# spinkler_02.net
KiCad netlist of a schematic drawn in EAGLE
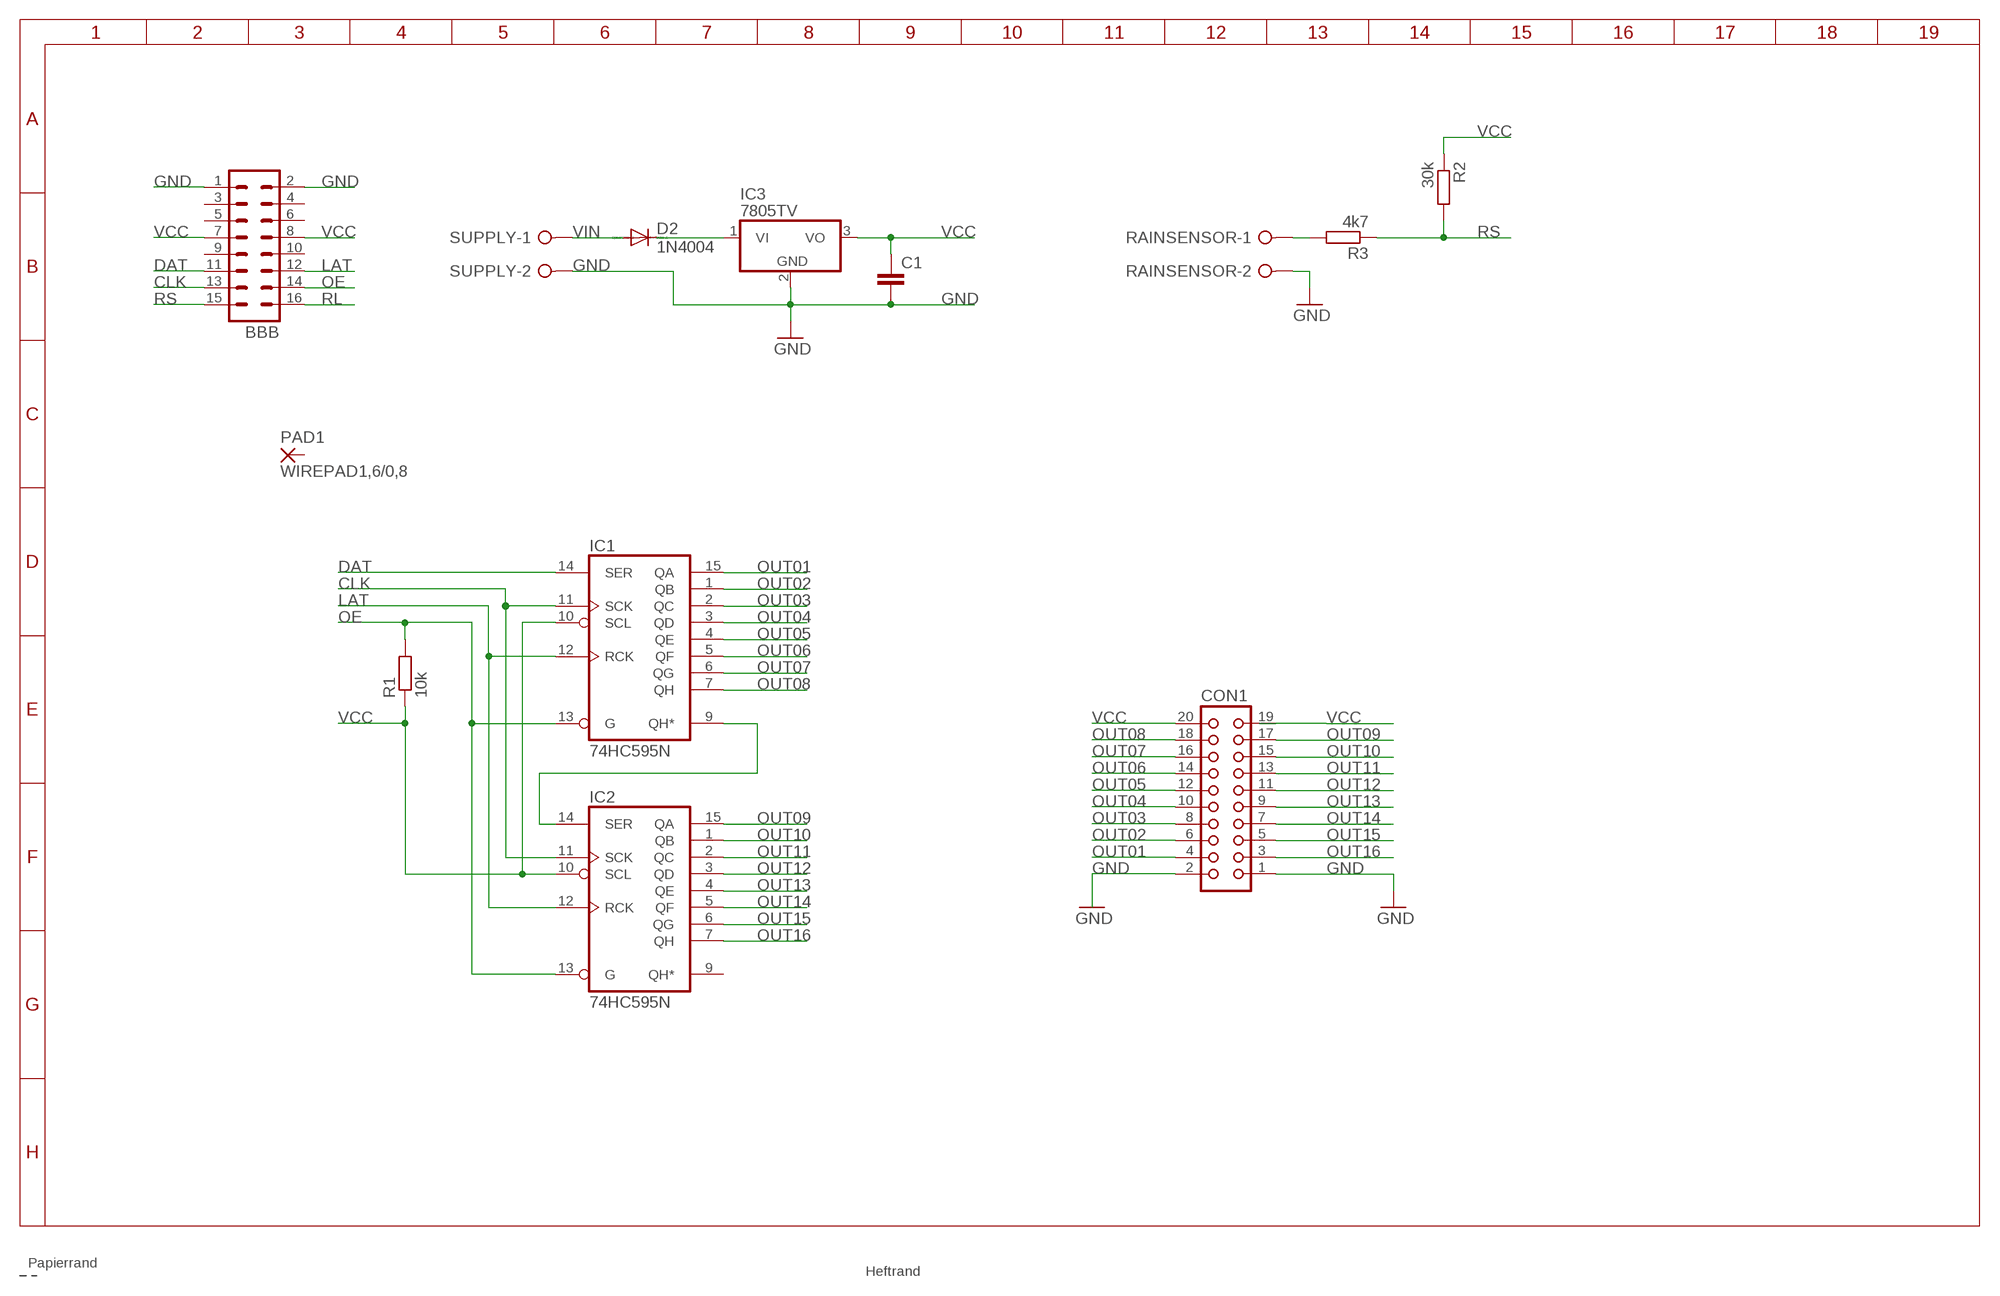
[diagram p0: schematic, sheet 1]

(export (version "E")
  (design (tool "Eeschema 10.0.6"))
  (components
    (comp (ref "BBB")
      (value "MA08-2")
      (footprint "eagle-import:MA08-2")
      (libsource (lib "eagle-import") (part "MA08-2"))
    )
    (comp (ref "C1")
      (value "C-EU050-025X075")
      (footprint "eagle-import:C050-025X075")
      (libsource (lib "eagle-import") (part "C-EU050-025X075"))
    )
    (comp (ref "CON1")
      (value "CON20")
      (footprint "eagle-import:CON20")
      (libsource (lib "eagle-import") (part "CON20"))
    )
    (comp (ref "D2")
      (value "1N4004")
      (footprint "eagle-import:DO41-10")
      (libsource (lib "eagle-import") (part "1N4004"))
    )
    (comp (ref "IC1")
      (value "74HC595N")
      (footprint "eagle-import:DIL16")
      (libsource (lib "eagle-import") (part "74595NHC"))
    )
    (comp (ref "IC2")
      (value "74HC595N")
      (footprint "eagle-import:DIL16")
      (libsource (lib "eagle-import") (part "74595NHC"))
    )
    (comp (ref "IC3")
      (value "7805TV")
      (footprint "eagle-import:TO220V")
      (libsource (lib "eagle-import") (part "78TV05"))
    )
    (comp (ref "PAD1")
      (value "WIREPAD1,6/0,8")
      (footprint "eagle-import:1,6_0,8")
      (libsource (lib "eagle-import") (part "WIREPAD1,6/0,8"))
    )
    (comp (ref "R1")
      (value "10k")
      (footprint "eagle-import:0207_10")
      (libsource (lib "eagle-import") (part "R-EU_0207/10"))
    )
    (comp (ref "R2")
      (value "30k")
      (footprint "eagle-import:0207_10")
      (libsource (lib "eagle-import") (part "R-EU_0207/10"))
    )
    (comp (ref "R3")
      (value "4k7")
      (footprint "eagle-import:0207_10")
      (libsource (lib "eagle-import") (part "R-EU_0207/10"))
    )
    (comp (ref "RAINSENSOR")
      (value "W237-02P")
      (footprint "eagle-import:W237-132")
      (libsource (lib "eagle-import") (part "W237-02P"))
    )
    (comp (ref "SUPPLY")
      (value "W237-02P")
      (footprint "eagle-import:W237-132")
      (libsource (lib "eagle-import") (part "W237-02P"))
    )
  )
  (nets
    (net (code "1") (name "/CLK") (class "Default")
      (node (ref "BBB") (pin "13") (pinfunction "13_13") (pintype "passive"))
      (node (ref "IC1") (pin "11") (pinfunction "SCK_11") (pintype "input"))
      (node (ref "IC2") (pin "11") (pinfunction "SCK_11") (pintype "input"))
    )
    (net (code "2") (name "/DAT") (class "Default")
      (node (ref "BBB") (pin "11") (pinfunction "11_11") (pintype "passive"))
      (node (ref "IC1") (pin "14") (pinfunction "SER_14") (pintype "input"))
    )
    (net (code "3") (name "/LAT") (class "Default")
      (node (ref "BBB") (pin "12") (pinfunction "12_12") (pintype "passive"))
      (node (ref "IC1") (pin "12") (pinfunction "RCK_12") (pintype "input"))
      (node (ref "IC2") (pin "12") (pinfunction "RCK_12") (pintype "input"))
    )
    (net (code "4") (name "/OE") (class "Default")
      (node (ref "BBB") (pin "14") (pinfunction "14_14") (pintype "passive"))
      (node (ref "IC1") (pin "13") (pinfunction "G_13") (pintype "input"))
      (node (ref "IC2") (pin "13") (pinfunction "G_13") (pintype "input"))
      (node (ref "R1") (pin "2") (pinfunction "2_2") (pintype "passive"))
    )
    (net (code "5") (name "/OUT01") (class "Default")
      (node (ref "CON1") (pin "4") (pinfunction "4_4") (pintype "passive"))
      (node (ref "IC1") (pin "15") (pinfunction "QA_15") (pintype "tri_state"))
    )
    (net (code "6") (name "/OUT02") (class "Default")
      (node (ref "CON1") (pin "6") (pinfunction "6_6") (pintype "passive"))
      (node (ref "IC1") (pin "1") (pinfunction "QB_1") (pintype "tri_state"))
    )
    (net (code "7") (name "/OUT03") (class "Default")
      (node (ref "CON1") (pin "8") (pinfunction "8_8") (pintype "passive"))
      (node (ref "IC1") (pin "2") (pinfunction "QC_2") (pintype "tri_state"))
    )
    (net (code "8") (name "/OUT04") (class "Default")
      (node (ref "CON1") (pin "10") (pinfunction "10_10") (pintype "passive"))
      (node (ref "IC1") (pin "3") (pinfunction "QD_3") (pintype "tri_state"))
    )
    (net (code "9") (name "/OUT05") (class "Default")
      (node (ref "CON1") (pin "12") (pinfunction "12_12") (pintype "passive"))
      (node (ref "IC1") (pin "4") (pinfunction "QE_4") (pintype "tri_state"))
    )
    (net (code "10") (name "/OUT06") (class "Default")
      (node (ref "CON1") (pin "14") (pinfunction "14_14") (pintype "passive"))
      (node (ref "IC1") (pin "5") (pinfunction "QF_5") (pintype "tri_state"))
    )
    (net (code "11") (name "/OUT07") (class "Default")
      (node (ref "CON1") (pin "16") (pinfunction "16_16") (pintype "passive"))
      (node (ref "IC1") (pin "6") (pinfunction "QG_6") (pintype "tri_state"))
    )
    (net (code "12") (name "/OUT08") (class "Default")
      (node (ref "CON1") (pin "18") (pinfunction "18_18") (pintype "passive"))
      (node (ref "IC1") (pin "7") (pinfunction "QH_7") (pintype "tri_state"))
    )
    (net (code "13") (name "/OUT09") (class "Default")
      (node (ref "CON1") (pin "17") (pinfunction "17_17") (pintype "passive"))
      (node (ref "IC2") (pin "15") (pinfunction "QA_15") (pintype "tri_state"))
    )
    (net (code "14") (name "/OUT10") (class "Default")
      (node (ref "CON1") (pin "15") (pinfunction "15_15") (pintype "passive"))
      (node (ref "IC2") (pin "1") (pinfunction "QB_1") (pintype "tri_state"))
    )
    (net (code "15") (name "/OUT11") (class "Default")
      (node (ref "CON1") (pin "13") (pinfunction "13_13") (pintype "passive"))
      (node (ref "IC2") (pin "2") (pinfunction "QC_2") (pintype "tri_state"))
    )
    (net (code "16") (name "/OUT12") (class "Default")
      (node (ref "CON1") (pin "11") (pinfunction "11_11") (pintype "passive"))
      (node (ref "IC2") (pin "3") (pinfunction "QD_3") (pintype "tri_state"))
    )
    (net (code "17") (name "/OUT13") (class "Default")
      (node (ref "CON1") (pin "9") (pinfunction "9_9") (pintype "passive"))
      (node (ref "IC2") (pin "4") (pinfunction "QE_4") (pintype "tri_state"))
    )
    (net (code "18") (name "/OUT14") (class "Default")
      (node (ref "CON1") (pin "7") (pinfunction "7_7") (pintype "passive"))
      (node (ref "IC2") (pin "5") (pinfunction "QF_5") (pintype "tri_state"))
    )
    (net (code "19") (name "/OUT15") (class "Default")
      (node (ref "CON1") (pin "5") (pinfunction "5_5") (pintype "passive"))
      (node (ref "IC2") (pin "6") (pinfunction "QG_6") (pintype "tri_state"))
    )
    (net (code "20") (name "/OUT16") (class "Default")
      (node (ref "CON1") (pin "3") (pinfunction "3_3") (pintype "passive"))
      (node (ref "IC2") (pin "7") (pinfunction "QH_7") (pintype "tri_state"))
    )
    (net (code "21") (name "/RL") (class "Default")
      (node (ref "BBB") (pin "16") (pinfunction "16_16") (pintype "passive"))
    )
    (net (code "22") (name "/RS") (class "Default")
      (node (ref "BBB") (pin "15") (pinfunction "15_15") (pintype "passive"))
      (node (ref "R2") (pin "2") (pinfunction "2_2") (pintype "passive"))
      (node (ref "R3") (pin "1") (pinfunction "1_1") (pintype "passive"))
    )
    (net (code "23") (name "/VCC") (class "Default")
      (node (ref "BBB") (pin "7") (pinfunction "7_7") (pintype "passive"))
      (node (ref "BBB") (pin "8") (pinfunction "8_8") (pintype "passive"))
      (node (ref "C1") (pin "1") (pinfunction "1_1") (pintype "passive"))
      (node (ref "CON1") (pin "19") (pinfunction "19_19") (pintype "passive"))
      (node (ref "CON1") (pin "20") (pinfunction "20_20") (pintype "passive"))
      (node (ref "IC1") (pin "10") (pinfunction "SCL_10") (pintype "input"))
      (node (ref "IC2") (pin "10") (pinfunction "SCL_10") (pintype "input"))
      (node (ref "IC3") (pin "3") (pinfunction "VO_3") (pintype "passive"))
      (node (ref "R1") (pin "1") (pinfunction "1_1") (pintype "passive"))
      (node (ref "R2") (pin "1") (pinfunction "1_1") (pintype "passive"))
    )
    (net (code "24") (name "/VIN") (class "Default")
      (node (ref "D2") (pin "A") (pinfunction "A_A") (pintype "passive"))
      (node (ref "SUPPLY") (pin "1") (pinfunction "KL_1") (pintype "passive"))
    )
    (net (code "25") (name "GND") (class "Default")
      (node (ref "BBB") (pin "1") (pinfunction "1_1") (pintype "passive"))
      (node (ref "BBB") (pin "2") (pinfunction "2_2") (pintype "passive"))
      (node (ref "C1") (pin "2") (pinfunction "2_2") (pintype "passive"))
      (node (ref "CON1") (pin "1") (pinfunction "1_1") (pintype "passive"))
      (node (ref "CON1") (pin "2") (pinfunction "2_2") (pintype "passive"))
      (node (ref "IC3") (pin "2") (pinfunction "GND_2") (pintype "passive"))
      (node (ref "RAINSENSOR") (pin "2") (pinfunction "KL_2") (pintype "passive"))
      (node (ref "SUPPLY") (pin "2") (pinfunction "KL_2") (pintype "passive"))
    )
    (net (code "26") (name "Net-(IC1A-QH*)") (class "Default")
      (node (ref "IC1") (pin "9") (pinfunction "QH*_9") (pintype "tri_state"))
      (node (ref "IC2") (pin "14") (pinfunction "SER_14") (pintype "input"))
    )
    (net (code "27") (name "Net-(IC3-VI)") (class "Default")
      (node (ref "D2") (pin "C") (pinfunction "C_C") (pintype "passive"))
      (node (ref "IC3") (pin "1") (pinfunction "VI_1") (pintype "input"))
    )
    (net (code "28") (name "Net-(RAINSENSORA-KL)") (class "Default")
      (node (ref "R3") (pin "2") (pinfunction "2_2") (pintype "passive"))
      (node (ref "RAINSENSOR") (pin "1") (pinfunction "KL_1") (pintype "passive"))
    )
    (net (code "29") (name "unconnected-(BBB-Pad3)") (class "Default")
      (node (ref "BBB") (pin "3") (pinfunction "3_3") (pintype "passive"))
    )
    (net (code "30") (name "unconnected-(BBB-Pad4)") (class "Default")
      (node (ref "BBB") (pin "4") (pinfunction "4_4") (pintype "passive"))
    )
    (net (code "31") (name "unconnected-(BBB-Pad5)") (class "Default")
      (node (ref "BBB") (pin "5") (pinfunction "5_5") (pintype "passive"))
    )
    (net (code "32") (name "unconnected-(BBB-Pad6)") (class "Default")
      (node (ref "BBB") (pin "6") (pinfunction "6_6") (pintype "passive"))
    )
    (net (code "33") (name "unconnected-(BBB-Pad9)") (class "Default")
      (node (ref "BBB") (pin "9") (pinfunction "9_9") (pintype "passive"))
    )
    (net (code "34") (name "unconnected-(BBB-Pad10)") (class "Default")
      (node (ref "BBB") (pin "10") (pinfunction "10_10") (pintype "passive"))
    )
    (net (code "35") (name "unconnected-(IC2A-QH*-Pad9)") (class "Default")
      (node (ref "IC2") (pin "9") (pinfunction "QH*_9") (pintype "tri_state"))
    )
    (net (code "36") (name "unconnected-(PAD1-P-Pad1)") (class "Default")
      (node (ref "PAD1") (pin "1") (pinfunction "P_1") (pintype "passive"))
    )
  )
)
